# TriFet.net
KiCad netlist of a schematic drawn in EAGLE
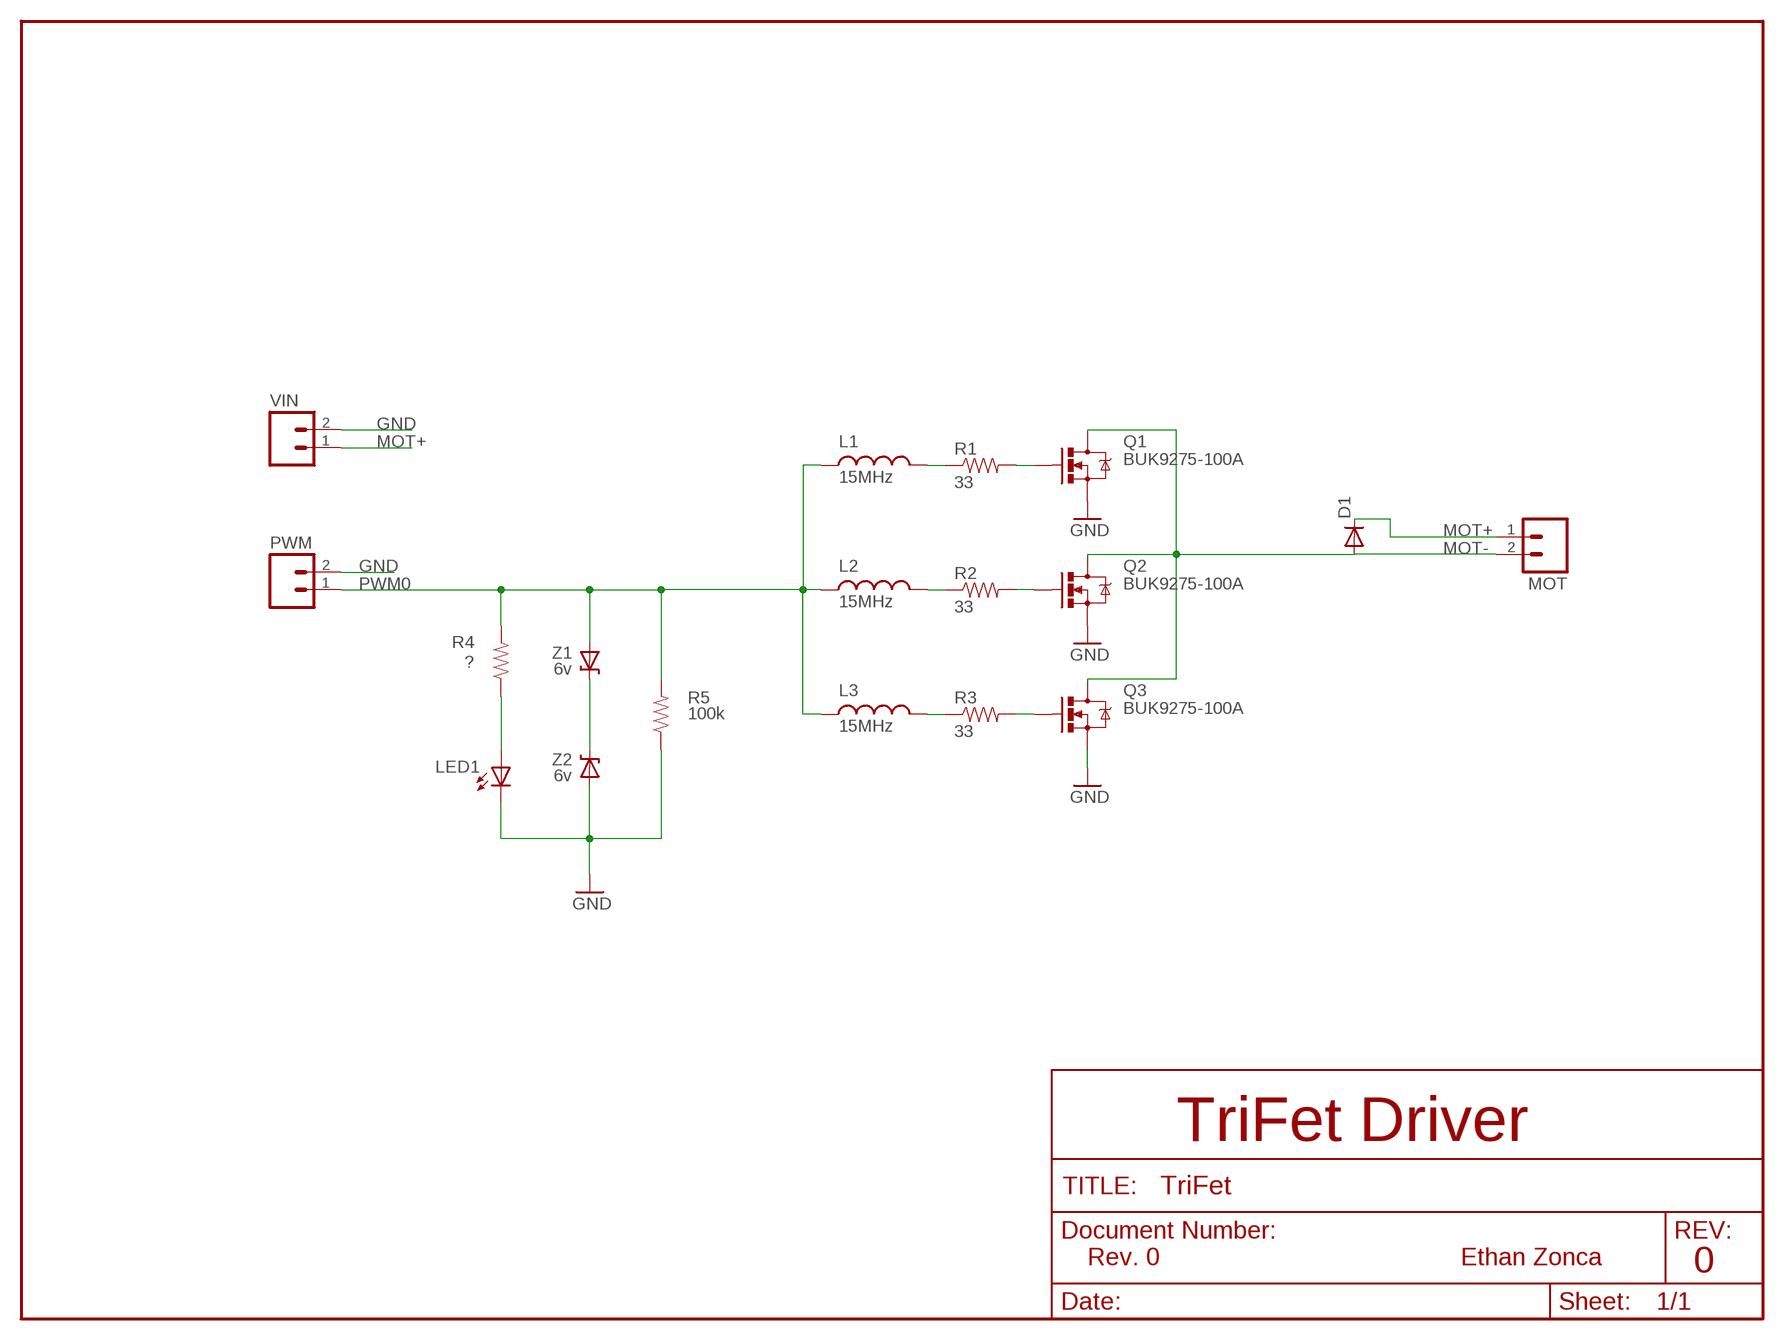
[diagram p0: schematic, sheet 1]

(export (version "E")
  (design (tool "Eeschema 10.0.6"))
  (components
    (comp (ref "D1")
      (value "DIODESMB")
      (footprint "eagle-import:SMB-DIODE")
      (libsource (lib "eagle-import") (part "DIODESMB"))
    )
    (comp (ref "L1")
      (value "15MHz")
      (footprint "eagle-import:0603")
      (libsource (lib "eagle-import") (part "INDUCTOR0603"))
    )
    (comp (ref "L2")
      (value "15MHz")
      (footprint "eagle-import:0603")
      (libsource (lib "eagle-import") (part "INDUCTOR0603"))
    )
    (comp (ref "L3")
      (value "15MHz")
      (footprint "eagle-import:0603")
      (libsource (lib "eagle-import") (part "INDUCTOR0603"))
    )
    (comp (ref "LED1")
      (value "LEDCHIP-LED0603")
      (footprint "eagle-import:CHIP-LED0603")
      (libsource (lib "eagle-import") (part "LEDCHIP-LED0603"))
    )
    (comp (ref "MOT")
      (value "M023.5MM")
      (footprint "eagle-import:SCREWTERMINAL-3.5MM-2")
      (libsource (lib "eagle-import") (part "M023.5MM"))
    )
    (comp (ref "PWM")
      (value "M023.5MM-NO_SILK")
      (footprint "eagle-import:SCREWTERMINAL-3.5MM-2-NS")
      (libsource (lib "eagle-import") (part "M023.5MM-NO_SILK"))
    )
    (comp (ref "Q1")
      (value "BUK9275-100A")
      (footprint "eagle-import:DPAK")
      (libsource (lib "eagle-import") (part "MOSFET-NCHANNELFDD8580"))
    )
    (comp (ref "Q2")
      (value "BUK9275-100A")
      (footprint "eagle-import:DPAK")
      (libsource (lib "eagle-import") (part "MOSFET-NCHANNELFDD8580"))
    )
    (comp (ref "Q3")
      (value "BUK9275-100A")
      (footprint "eagle-import:DPAK")
      (libsource (lib "eagle-import") (part "MOSFET-NCHANNELFDD8580"))
    )
    (comp (ref "R1")
      (value "33")
      (footprint "eagle-import:0603-RES")
      (libsource (lib "eagle-import") (part "RESISTOR0603-RES"))
    )
    (comp (ref "R2")
      (value "33")
      (footprint "eagle-import:0603-RES")
      (libsource (lib "eagle-import") (part "RESISTOR0603-RES"))
    )
    (comp (ref "R3")
      (value "33")
      (footprint "eagle-import:0603-RES")
      (libsource (lib "eagle-import") (part "RESISTOR0603-RES"))
    )
    (comp (ref "R4")
      (value "?")
      (footprint "eagle-import:0603-RES")
      (libsource (lib "eagle-import") (part "RESISTOR0603-RES"))
    )
    (comp (ref "R5")
      (value "100k")
      (footprint "eagle-import:0603-RES")
      (libsource (lib "eagle-import") (part "RESISTOR0603-RES"))
    )
    (comp (ref "VIN")
      (value "M023.5MM-NO_SILK")
      (footprint "eagle-import:SCREWTERMINAL-3.5MM-2-NS")
      (libsource (lib "eagle-import") (part "M023.5MM-NO_SILK"))
    )
    (comp (ref "Z1")
      (value "6v")
      (footprint "eagle-import:SOD-323")
      (libsource (lib "eagle-import") (part "DIODE-ZENER-BZT52"))
    )
    (comp (ref "Z2")
      (value "6v")
      (footprint "eagle-import:SOD-323")
      (libsource (lib "eagle-import") (part "DIODE-ZENER-BZT52"))
    )
  )
  (nets
    (net (code "1") (name "/MOT+") (class "Default")
      (node (ref "D1") (pin "C") (pinfunction "C_C") (pintype "passive"))
      (node (ref "MOT") (pin "1") (pinfunction "1_1") (pintype "passive"))
      (node (ref "VIN") (pin "1") (pinfunction "1_1") (pintype "passive"))
    )
    (net (code "2") (name "/MOT-") (class "Default")
      (node (ref "D1") (pin "A") (pinfunction "A_A") (pintype "passive"))
      (node (ref "MOT") (pin "2") (pinfunction "2_2") (pintype "passive"))
      (node (ref "Q1") (pin "4") (pinfunction "D_4") (pintype "passive"))
      (node (ref "Q2") (pin "4") (pinfunction "D_4") (pintype "passive"))
      (node (ref "Q3") (pin "4") (pinfunction "D_4") (pintype "passive"))
    )
    (net (code "3") (name "/PWM0") (class "Default")
      (node (ref "L1") (pin "1") (pinfunction "1_1") (pintype "passive"))
      (node (ref "L2") (pin "1") (pinfunction "1_1") (pintype "passive"))
      (node (ref "L3") (pin "1") (pinfunction "1_1") (pintype "passive"))
      (node (ref "PWM") (pin "1") (pinfunction "1_1") (pintype "passive"))
      (node (ref "R4") (pin "2") (pinfunction "2_2") (pintype "passive"))
      (node (ref "R5") (pin "2") (pinfunction "2_2") (pintype "passive"))
      (node (ref "Z1") (pin "2") (pinfunction "A_2") (pintype "passive"))
    )
    (net (code "4") (name "GND") (class "Default")
      (node (ref "LED1") (pin "C") (pinfunction "C_C") (pintype "passive"))
      (node (ref "PWM") (pin "2") (pinfunction "2_2") (pintype "passive"))
      (node (ref "Q1") (pin "3") (pinfunction "S_3") (pintype "passive"))
      (node (ref "Q2") (pin "3") (pinfunction "S_3") (pintype "passive"))
      (node (ref "Q3") (pin "3") (pinfunction "S_3") (pintype "passive"))
      (node (ref "R5") (pin "1") (pinfunction "1_1") (pintype "passive"))
      (node (ref "VIN") (pin "2") (pinfunction "2_2") (pintype "passive"))
      (node (ref "Z2") (pin "2") (pinfunction "A_2") (pintype "passive"))
    )
    (net (code "5") (name "Net-(L1-Pad2)") (class "Default")
      (node (ref "L1") (pin "2") (pinfunction "2_2") (pintype "passive"))
      (node (ref "R1") (pin "1") (pinfunction "1_1") (pintype "passive"))
    )
    (net (code "6") (name "Net-(L2-Pad2)") (class "Default")
      (node (ref "L2") (pin "2") (pinfunction "2_2") (pintype "passive"))
      (node (ref "R2") (pin "1") (pinfunction "1_1") (pintype "passive"))
    )
    (net (code "7") (name "Net-(L3-Pad2)") (class "Default")
      (node (ref "L3") (pin "2") (pinfunction "2_2") (pintype "passive"))
      (node (ref "R3") (pin "1") (pinfunction "1_1") (pintype "passive"))
    )
    (net (code "8") (name "Net-(LED1-PadA)") (class "Default")
      (node (ref "LED1") (pin "A") (pinfunction "A_A") (pintype "passive"))
      (node (ref "R4") (pin "1") (pinfunction "1_1") (pintype "passive"))
    )
    (net (code "9") (name "Net-(Q1-G)") (class "Default")
      (node (ref "Q1") (pin "1") (pinfunction "G_1") (pintype "passive"))
      (node (ref "R1") (pin "2") (pinfunction "2_2") (pintype "passive"))
    )
    (net (code "10") (name "Net-(Q2-G)") (class "Default")
      (node (ref "Q2") (pin "1") (pinfunction "G_1") (pintype "passive"))
      (node (ref "R2") (pin "2") (pinfunction "2_2") (pintype "passive"))
    )
    (net (code "11") (name "Net-(Q3-G)") (class "Default")
      (node (ref "Q3") (pin "1") (pinfunction "G_1") (pintype "passive"))
      (node (ref "R3") (pin "2") (pinfunction "2_2") (pintype "passive"))
    )
    (net (code "12") (name "Net-(Z1-C)") (class "Default")
      (node (ref "Z1") (pin "1") (pinfunction "C_1") (pintype "passive"))
      (node (ref "Z2") (pin "1") (pinfunction "C_1") (pintype "passive"))
    )
  )
)
